# BSPD_V2_1.net
KiCad netlist of a schematic drawn in Altium Designer
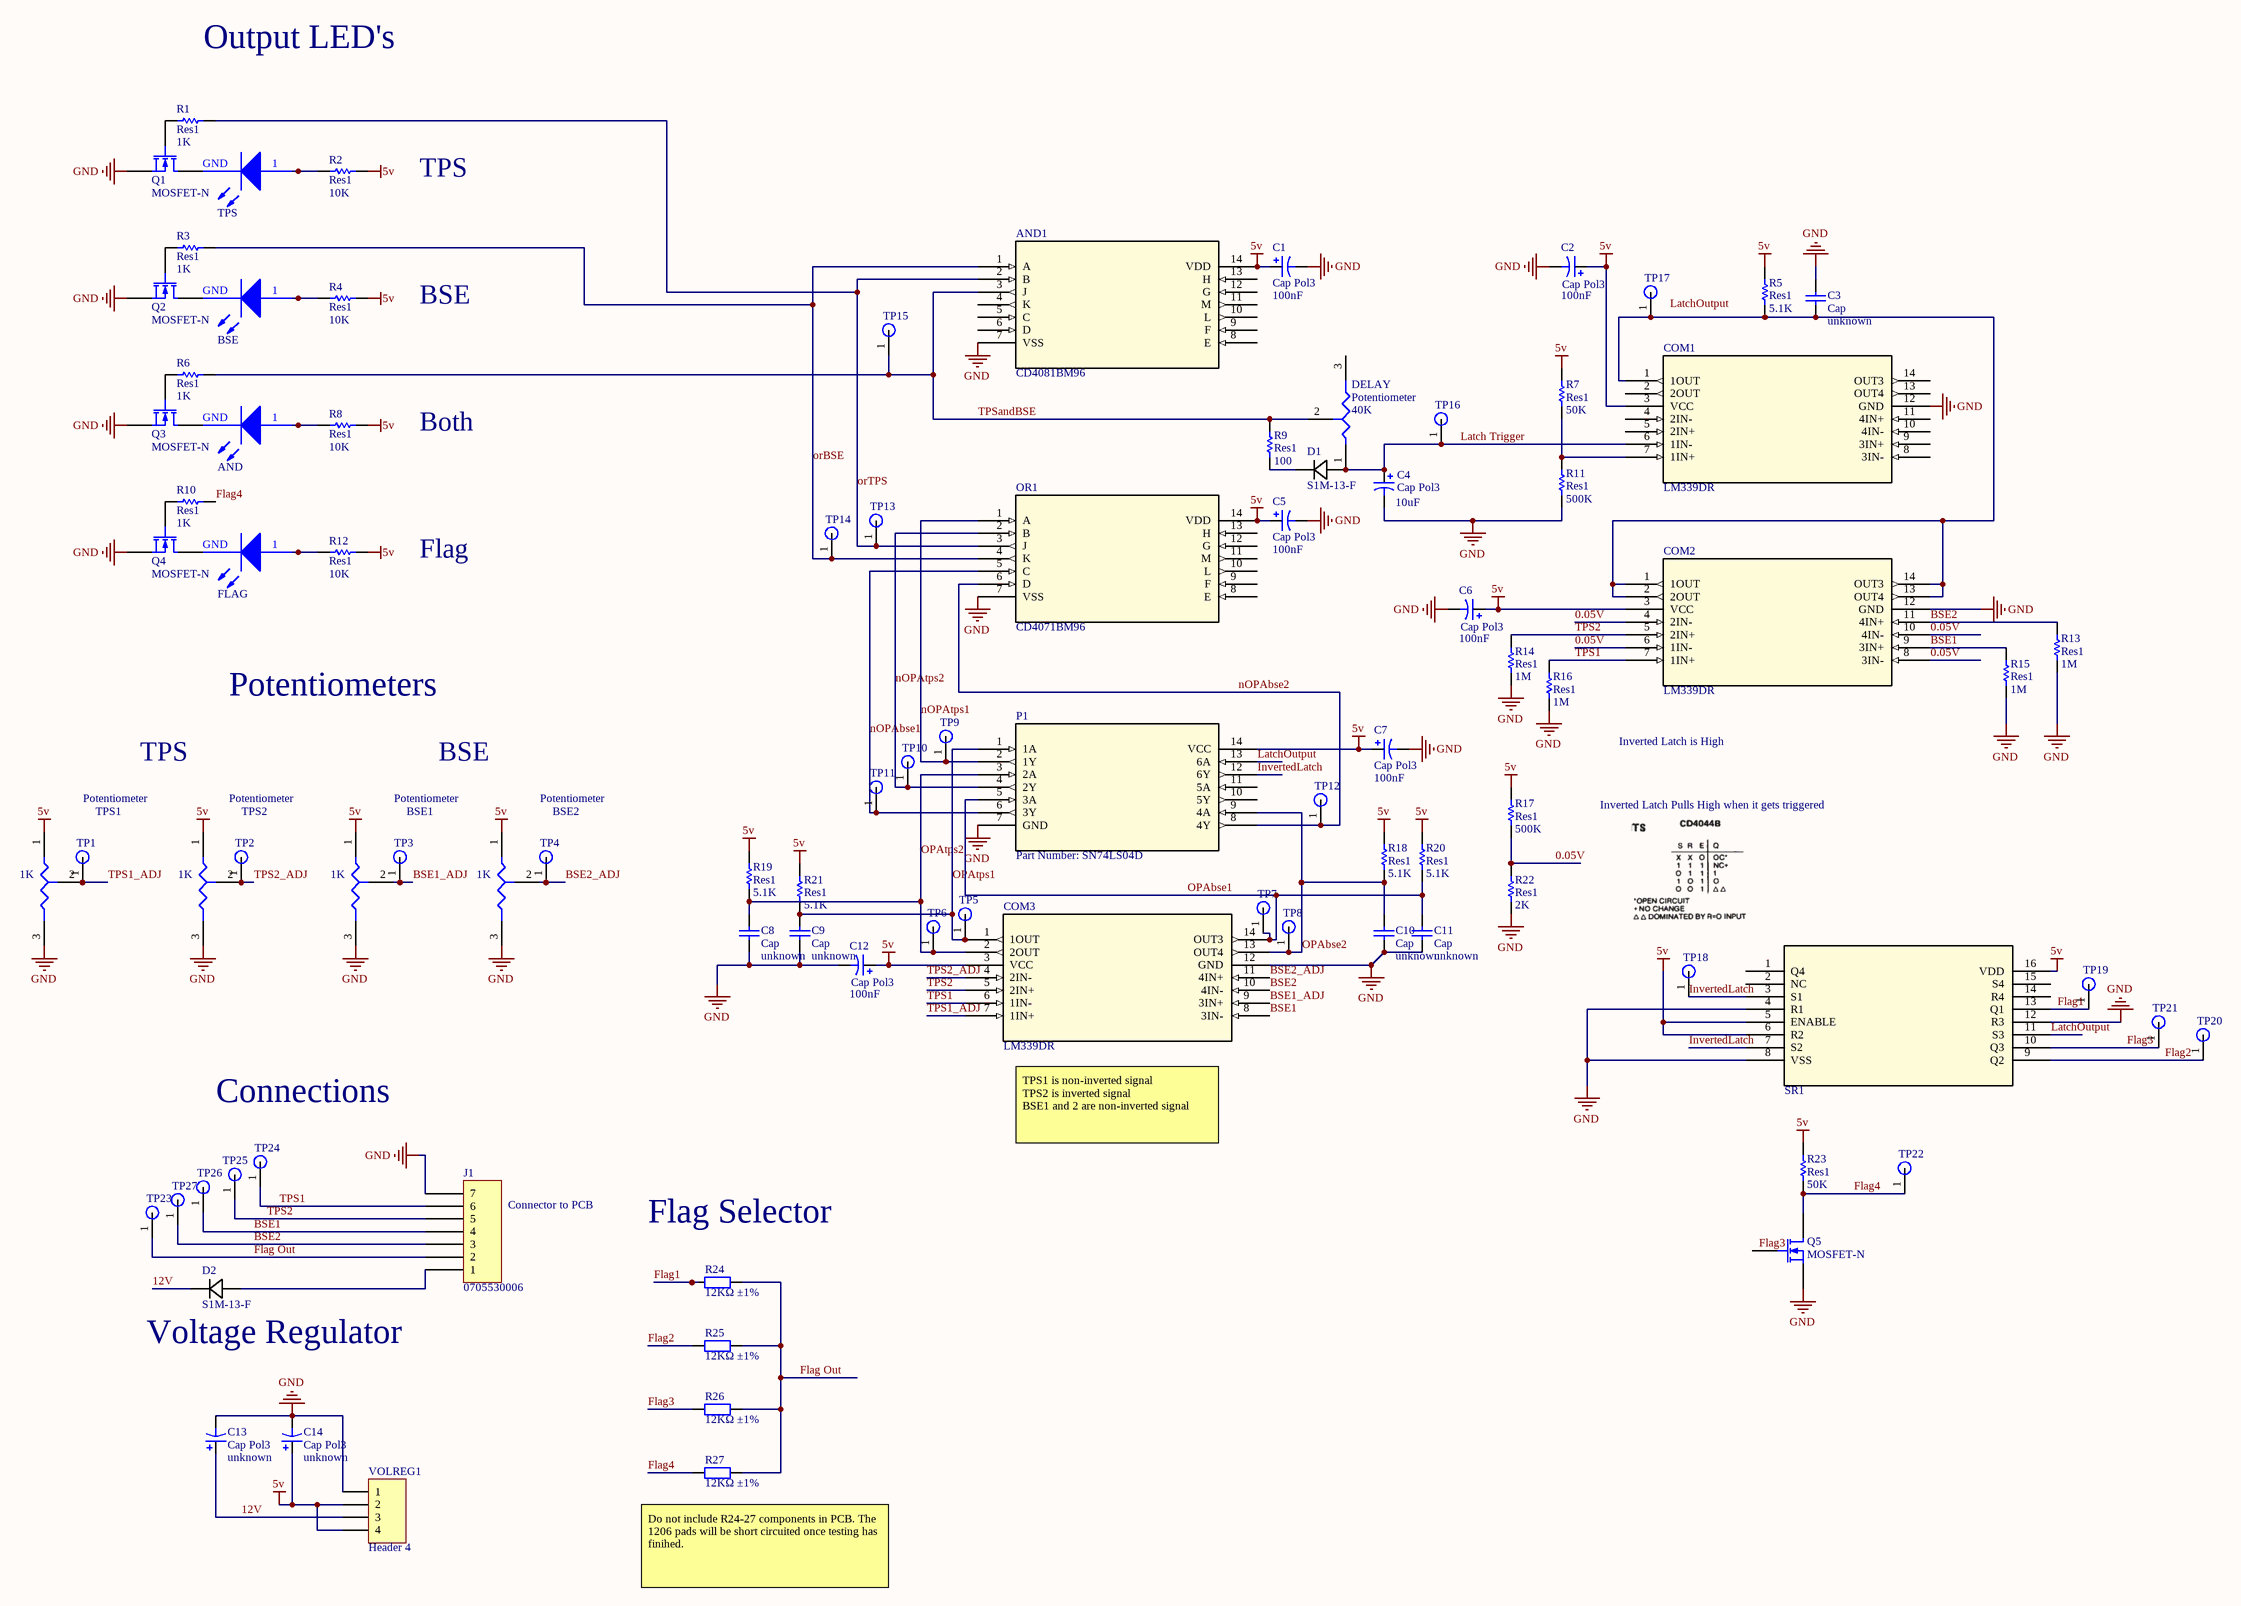
[diagram p0: BSPD_V2.1.SchDoc]

(export (version "E")
  (design (tool "Eeschema 10.0.6"))
  (components
    (comp (ref "AND")
      (value "Green Led")
      (footprint "Single_Color_LED")
      (description "DK: 1497-1160-1-ND Ζ MF: XZM2DG45SB")
      (libsource (lib "AltiumDesigner") (part "Green_LED"))
    )
    (comp (ref "AND1")
      (value "CD4081BM96")
      (footprint "D14")
      (description "Imported")
      (libsource (lib "AltiumDesigner") (part "CD4081BM96"))
    )
    (comp (ref "BSE")
      (value "Green Led")
      (footprint "Single_Color_LED")
      (description "DK: 1497-1160-1-ND Ζ MF: XZM2DG45SB")
      (libsource (lib "AltiumDesigner") (part "Green_LED"))
    )
    (comp (ref "BSE1")
      (value "Potentiometer")
      (footprint "Potentiometers")
      (description "Tapped Resistor")
      (fields (field (name "ALTIUM_VALUE") "1K") (field (name "PUBLISHER") "Altium Limited"))
      (libsource (lib "BSPD_Library") (part "Potentiometer"))
    )
    (comp (ref "BSE2")
      (value "Potentiometer")
      (footprint "Potentiometers")
      (description "Tapped Resistor")
      (fields (field (name "ALTIUM_VALUE") "1K") (field (name "PUBLISHER") "Altium Limited"))
      (libsource (lib "BSPD_Library") (part "Potentiometer"))
    )
    (comp (ref "C1")
      (value "Cap Pol3")
      (footprint "RC0805N")
      (description "Polarized Capacitor (Surface Mount)")
      (fields (field (name "ALTIUM_VALUE") "100nF") (field (name "PUBLISHER") "Altium Limited"))
      (libsource (lib "Miscellaneous Devices") (part "Cap Pol3"))
    )
    (comp (ref "C2")
      (value "Cap Pol3")
      (footprint "RC0805N")
      (description "Polarized Capacitor (Surface Mount)")
      (fields (field (name "ALTIUM_VALUE") "100nF") (field (name "PUBLISHER") "Altium Limited"))
      (libsource (lib "Miscellaneous Devices") (part "Cap Pol3"))
    )
    (comp (ref "C3")
      (value "Cap")
      (footprint "RC0805N")
      (description "Capacitor")
      (fields (field (name "ALTIUM_VALUE") "unknown") (field (name "PUBLISHER") "Altium Limited"))
      (libsource (lib "Miscellaneous Devices") (part "Cap"))
    )
    (comp (ref "C4")
      (value "Cap Pol3")
      (footprint "RC0805N")
      (description "Polarized Capacitor (Surface Mount)")
      (fields (field (name "ALTIUM_VALUE") "10uF") (field (name "PUBLISHER") "Altium Limited"))
      (libsource (lib "Miscellaneous Devices") (part "Cap Pol3"))
    )
    (comp (ref "C5")
      (value "Cap Pol3")
      (footprint "RC0805N")
      (description "Polarized Capacitor (Surface Mount)")
      (fields (field (name "ALTIUM_VALUE") "100nF") (field (name "PUBLISHER") "Altium Limited"))
      (libsource (lib "Miscellaneous Devices") (part "Cap Pol3"))
    )
    (comp (ref "C6")
      (value "Cap Pol3")
      (footprint "RC0805N")
      (description "Polarized Capacitor (Surface Mount)")
      (fields (field (name "ALTIUM_VALUE") "100nF") (field (name "PUBLISHER") "Altium Limited"))
      (libsource (lib "Miscellaneous Devices") (part "Cap Pol3"))
    )
    (comp (ref "C7")
      (value "Cap Pol3")
      (footprint "RC0805N")
      (description "Polarized Capacitor (Surface Mount)")
      (fields (field (name "ALTIUM_VALUE") "100nF") (field (name "PUBLISHER") "Altium Limited"))
      (libsource (lib "Miscellaneous Devices") (part "Cap Pol3"))
    )
    (comp (ref "C8")
      (value "Cap")
      (footprint "RC0805N")
      (description "Capacitor")
      (fields (field (name "ALTIUM_VALUE") "unknown") (field (name "PUBLISHER") "Altium Limited"))
      (libsource (lib "Miscellaneous Devices") (part "Cap"))
    )
    (comp (ref "C9")
      (value "Cap")
      (footprint "RC0805N")
      (description "Capacitor")
      (fields (field (name "ALTIUM_VALUE") "unknown") (field (name "PUBLISHER") "Altium Limited"))
      (libsource (lib "Miscellaneous Devices") (part "Cap"))
    )
    (comp (ref "C10")
      (value "Cap")
      (footprint "RC0805N")
      (description "Capacitor")
      (fields (field (name "ALTIUM_VALUE") "unknown") (field (name "PUBLISHER") "Altium Limited"))
      (libsource (lib "Miscellaneous Devices") (part "Cap"))
    )
    (comp (ref "C11")
      (value "Cap")
      (footprint "RC0805N")
      (description "Capacitor")
      (fields (field (name "ALTIUM_VALUE") "unknown") (field (name "PUBLISHER") "Altium Limited"))
      (libsource (lib "Miscellaneous Devices") (part "Cap"))
    )
    (comp (ref "C12")
      (value "Cap Pol3")
      (footprint "RC0805N")
      (description "Polarized Capacitor (Surface Mount)")
      (fields (field (name "ALTIUM_VALUE") "100nF") (field (name "PUBLISHER") "Altium Limited"))
      (libsource (lib "Miscellaneous Devices") (part "Cap Pol3"))
    )
    (comp (ref "C13")
      (value "Cap Pol3")
      (footprint "RC0805N")
      (description "Polarized Capacitor (Surface Mount)")
      (fields (field (name "ALTIUM_VALUE") "unknown") (field (name "PUBLISHER") "Altium Limited"))
      (libsource (lib "Miscellaneous Devices") (part "Cap Pol3"))
    )
    (comp (ref "C14")
      (value "Cap Pol3")
      (footprint "RC0805N")
      (description "Polarized Capacitor (Surface Mount)")
      (fields (field (name "ALTIUM_VALUE") "unknown") (field (name "PUBLISHER") "Altium Limited"))
      (libsource (lib "Miscellaneous Devices") (part "Cap Pol3"))
    )
    (comp (ref "COM1")
      (value "LM339DR")
      (footprint "D14")
      (description "Imported")
      (fields (field (name "MANUFACTURER") "Texas Instruments"))
      (libsource (lib "AltiumDesigner") (part "LM339DR"))
    )
    (comp (ref "COM2")
      (value "LM339DR")
      (footprint "D14")
      (description "Imported")
      (fields (field (name "MANUFACTURER") "Texas Instruments"))
      (libsource (lib "AltiumDesigner") (part "LM339DR"))
    )
    (comp (ref "COM3")
      (value "LM339DR")
      (footprint "D14")
      (description "Imported")
      (fields (field (name "MANUFACTURER") "Texas Instruments"))
      (libsource (lib "AltiumDesigner") (part "LM339DR"))
    )
    (comp (ref "D1")
      (value "S1M-13-F")
      (footprint "DIODE")
      (description "Imported")
      (libsource (lib "AltiumDesigner") (part "S1M-13-F"))
    )
    (comp (ref "D2")
      (value "S1M-13-F")
      (footprint "DIODE")
      (description "Imported")
      (libsource (lib "AltiumDesigner") (part "S1M-13-F"))
    )
    (comp (ref "DELAY")
      (value "Potentiometer")
      (footprint "Potentiometers")
      (description "Tapped Resistor")
      (fields (field (name "ALTIUM_VALUE") "40K") (field (name "PUBLISHER") "Altium Limited"))
      (libsource (lib "BSPD_Library") (part "Potentiometer"))
    )
    (comp (ref "FLAG")
      (value "Green Led")
      (footprint "Single_Color_LED")
      (description "DK: 1497-1160-1-ND Ζ MF: XZM2DG45SB")
      (libsource (lib "AltiumDesigner") (part "Green_LED"))
    )
    (comp (ref "J1")
      (value "0705530006")
      (footprint "MOLEX SDA-70553-7PIN")
      (description "CONN HEADER R/A 7POS 2.54MM")
      (fields (field (name "MANUFACTURER") "Molex"))
      (libsource (lib "Celestial Altium Library - altium_library") (part "7 Pin"))
    )
    (comp (ref "OR1")
      (value "CD4071BM96")
      (footprint "D14")
      (description "Imported")
      (libsource (lib "AltiumDesigner") (part "CD4071BM96"))
    )
    (comp (ref "P1")
      (value "Part Number: SN74LS04D")
      (footprint "D14")
      (description "No Description Available")
      (fields
        (field (name "MANUFACTURER_PART_NUMBER") "SN74LS04D")
        (field (name "COPYRIGHT") "Copyright (C) 2018 Accelerated Designs. All rights reserved")
      )
      (libsource (lib "AltiumDesigner") (part "SN74LS04D"))
    )
    (comp (ref "Q1")
      (value "MOSFET-N")
      (footprint "SOT-23-3")
      (description "N-Channel MOSFET")
      (fields (field (name "PUBLISHER") "Altium Limited"))
      (libsource (lib "Miscellaneous Devices") (part "MOSFET-N"))
    )
    (comp (ref "Q2")
      (value "MOSFET-N")
      (footprint "SOT-23-3")
      (description "N-Channel MOSFET")
      (fields (field (name "PUBLISHER") "Altium Limited"))
      (libsource (lib "Miscellaneous Devices") (part "MOSFET-N"))
    )
    (comp (ref "Q3")
      (value "MOSFET-N")
      (footprint "SOT-23-3")
      (description "N-Channel MOSFET")
      (fields (field (name "PUBLISHER") "Altium Limited"))
      (libsource (lib "Miscellaneous Devices") (part "MOSFET-N"))
    )
    (comp (ref "Q4")
      (value "MOSFET-N")
      (footprint "SOT-23-3")
      (description "N-Channel MOSFET")
      (fields (field (name "PUBLISHER") "Altium Limited"))
      (libsource (lib "Miscellaneous Devices") (part "MOSFET-N"))
    )
    (comp (ref "Q5")
      (value "MOSFET-N")
      (footprint "SOT-23-3")
      (description "N-Channel MOSFET")
      (fields (field (name "PUBLISHER") "Altium Limited"))
      (libsource (lib "Miscellaneous Devices") (part "MOSFET-N"))
    )
    (comp (ref "R1")
      (value "Res1")
      (footprint "RC0805N")
      (description "Resistor")
      (fields (field (name "ALTIUM_VALUE") "1K") (field (name "PUBLISHER") "Altium Limited"))
      (libsource (lib "Miscellaneous Devices") (part "Res1"))
    )
    (comp (ref "R2")
      (value "Res1")
      (footprint "RC0805N")
      (description "Resistor")
      (fields (field (name "ALTIUM_VALUE") "10K") (field (name "PUBLISHER") "Altium Limited"))
      (libsource (lib "Miscellaneous Devices") (part "Res1"))
    )
    (comp (ref "R3")
      (value "Res1")
      (footprint "RC0805N")
      (description "Resistor")
      (fields (field (name "ALTIUM_VALUE") "1K") (field (name "PUBLISHER") "Altium Limited"))
      (libsource (lib "Miscellaneous Devices") (part "Res1"))
    )
    (comp (ref "R4")
      (value "Res1")
      (footprint "RC0805N")
      (description "Resistor")
      (fields (field (name "ALTIUM_VALUE") "10K") (field (name "PUBLISHER") "Altium Limited"))
      (libsource (lib "Miscellaneous Devices") (part "Res1"))
    )
    (comp (ref "R5")
      (value "Res1")
      (footprint "RC0805N")
      (description "Resistor")
      (fields (field (name "ALTIUM_VALUE") "5.1K") (field (name "PUBLISHER") "Altium Limited"))
      (libsource (lib "Miscellaneous Devices") (part "Res1"))
    )
    (comp (ref "R6")
      (value "Res1")
      (footprint "RC0805N")
      (description "Resistor")
      (fields (field (name "ALTIUM_VALUE") "1K") (field (name "PUBLISHER") "Altium Limited"))
      (libsource (lib "Miscellaneous Devices") (part "Res1"))
    )
    (comp (ref "R7")
      (value "Res1")
      (footprint "RC0805N")
      (description "Resistor")
      (fields (field (name "ALTIUM_VALUE") "50K") (field (name "PUBLISHER") "Altium Limited"))
      (libsource (lib "Miscellaneous Devices") (part "Res1"))
    )
    (comp (ref "R8")
      (value "Res1")
      (footprint "RC0805N")
      (description "Resistor")
      (fields (field (name "ALTIUM_VALUE") "10K") (field (name "PUBLISHER") "Altium Limited"))
      (libsource (lib "Miscellaneous Devices") (part "Res1"))
    )
    (comp (ref "R9")
      (value "Res1")
      (footprint "RC0805N")
      (description "Resistor")
      (fields (field (name "ALTIUM_VALUE") "100") (field (name "PUBLISHER") "Altium Limited"))
      (libsource (lib "Miscellaneous Devices") (part "Res1"))
    )
    (comp (ref "R10")
      (value "Res1")
      (footprint "RC0805N")
      (description "Resistor")
      (fields (field (name "ALTIUM_VALUE") "1K") (field (name "PUBLISHER") "Altium Limited"))
      (libsource (lib "Miscellaneous Devices") (part "Res1"))
    )
    (comp (ref "R11")
      (value "Res1")
      (footprint "RC0805N")
      (description "Resistor")
      (fields (field (name "ALTIUM_VALUE") "500K") (field (name "PUBLISHER") "Altium Limited"))
      (libsource (lib "Miscellaneous Devices") (part "Res1"))
    )
    (comp (ref "R12")
      (value "Res1")
      (footprint "RC0805N")
      (description "Resistor")
      (fields (field (name "ALTIUM_VALUE") "10K") (field (name "PUBLISHER") "Altium Limited"))
      (libsource (lib "Miscellaneous Devices") (part "Res1"))
    )
    (comp (ref "R13")
      (value "Res1")
      (footprint "RC0805N")
      (description "Resistor")
      (fields (field (name "ALTIUM_VALUE") "1M") (field (name "PUBLISHER") "Altium Limited"))
      (libsource (lib "Miscellaneous Devices") (part "Res1"))
    )
    (comp (ref "R14")
      (value "Res1")
      (footprint "RC0805N")
      (description "Resistor")
      (fields (field (name "ALTIUM_VALUE") "1M") (field (name "PUBLISHER") "Altium Limited"))
      (libsource (lib "Miscellaneous Devices") (part "Res1"))
    )
    (comp (ref "R15")
      (value "Res1")
      (footprint "RC0805N")
      (description "Resistor")
      (fields (field (name "ALTIUM_VALUE") "1M") (field (name "PUBLISHER") "Altium Limited"))
      (libsource (lib "Miscellaneous Devices") (part "Res1"))
    )
    (comp (ref "R16")
      (value "Res1")
      (footprint "RC0805N")
      (description "Resistor")
      (fields (field (name "ALTIUM_VALUE") "1M") (field (name "PUBLISHER") "Altium Limited"))
      (libsource (lib "Miscellaneous Devices") (part "Res1"))
    )
    (comp (ref "R17")
      (value "Res1")
      (footprint "RC0805N")
      (description "Resistor")
      (fields (field (name "ALTIUM_VALUE") "500K") (field (name "PUBLISHER") "Altium Limited"))
      (libsource (lib "Miscellaneous Devices") (part "Res1"))
    )
    (comp (ref "R18")
      (value "Res1")
      (footprint "RC0805N")
      (description "Resistor")
      (fields (field (name "ALTIUM_VALUE") "5.1K") (field (name "PUBLISHER") "Altium Limited"))
      (libsource (lib "Miscellaneous Devices") (part "Res1"))
    )
    (comp (ref "R19")
      (value "Res1")
      (footprint "RC0805N")
      (description "Resistor")
      (fields (field (name "ALTIUM_VALUE") "5.1K") (field (name "PUBLISHER") "Altium Limited"))
      (libsource (lib "Miscellaneous Devices") (part "Res1"))
    )
    (comp (ref "R20")
      (value "Res1")
      (footprint "RC0805N")
      (description "Resistor")
      (fields (field (name "ALTIUM_VALUE") "5.1K") (field (name "PUBLISHER") "Altium Limited"))
      (libsource (lib "Miscellaneous Devices") (part "Res1"))
    )
    (comp (ref "R21")
      (value "Res1")
      (footprint "RC0805N")
      (description "Resistor")
      (fields (field (name "ALTIUM_VALUE") "5.1K") (field (name "PUBLISHER") "Altium Limited"))
      (libsource (lib "Miscellaneous Devices") (part "Res1"))
    )
    (comp (ref "R22")
      (value "Res1")
      (footprint "RC0805N")
      (description "Resistor")
      (fields (field (name "ALTIUM_VALUE") "2K") (field (name "PUBLISHER") "Altium Limited"))
      (libsource (lib "Miscellaneous Devices") (part "Res1"))
    )
    (comp (ref "R23")
      (value "Res1")
      (footprint "RC0805N")
      (description "Resistor")
      (fields (field (name "ALTIUM_VALUE") "50K") (field (name "PUBLISHER") "Altium Limited"))
      (libsource (lib "Miscellaneous Devices") (part "Res1"))
    )
    (comp (ref "R24")
      (value "12KΩ ±1%")
      (footprint "0805_R")
      (description "Chip resistor")
      (fields (field (name "MANUFACTURER") "Uniroyal Elec") (field (name "POWER") "1/8W"))
      (libsource (lib "RES") (part "0805 12K (1202) 1%"))
    )
    (comp (ref "R25")
      (value "12KΩ ±1%")
      (footprint "0805_R")
      (description "Chip resistor")
      (fields (field (name "MANUFACTURER") "Uniroyal Elec") (field (name "POWER") "1/8W"))
      (libsource (lib "RES") (part "0805 12K (1202) 1%"))
    )
    (comp (ref "R26")
      (value "12KΩ ±1%")
      (footprint "0805_R")
      (description "Chip resistor")
      (fields (field (name "MANUFACTURER") "Uniroyal Elec") (field (name "POWER") "1/8W"))
      (libsource (lib "RES") (part "0805 12K (1202) 1%"))
    )
    (comp (ref "R27")
      (value "12KΩ ±1%")
      (footprint "0805_R")
      (description "Chip resistor")
      (fields (field (name "MANUFACTURER") "Uniroyal Elec") (field (name "POWER") "1/8W"))
      (libsource (lib "RES") (part "0805 12K (1202) 1%"))
    )
    (comp (ref "SR1")
      (value "CD4044BNSR")
      (footprint "NS16")
      (description "IC QUAD NAND R/S LATCH 16SO")
      (libsource (lib "QFSAE_ELEC") (part "SR Latch Quad"))
    )
    (comp (ref "TP1") (value "Test Point") (footprint "TP1") (libsource (lib "ethan") (part "TP1")))
    (comp (ref "TP2") (value "Test Point") (footprint "TP1") (libsource (lib "ethan") (part "TP1")))
    (comp (ref "TP3") (value "Test Point") (footprint "TP1") (libsource (lib "ethan") (part "TP1")))
    (comp (ref "TP4") (value "Test Point") (footprint "TP1") (libsource (lib "ethan") (part "TP1")))
    (comp (ref "TP5") (value "Test Point") (footprint "TP1") (libsource (lib "ethan") (part "TP1")))
    (comp (ref "TP6") (value "Test Point") (footprint "TP1") (libsource (lib "ethan") (part "TP1")))
    (comp (ref "TP7") (value "Test Point") (footprint "TP1") (libsource (lib "ethan") (part "TP1")))
    (comp (ref "TP8") (value "Test Point") (footprint "TP1") (libsource (lib "ethan") (part "TP1")))
    (comp (ref "TP9") (value "Test Point") (footprint "TP1") (libsource (lib "ethan") (part "TP1")))
    (comp (ref "TP10") (value "Test Point") (footprint "TP1") (libsource (lib "ethan") (part "TP1")))
    (comp (ref "TP11") (value "Test Point") (footprint "TP1") (libsource (lib "ethan") (part "TP1")))
    (comp (ref "TP12") (value "Test Point") (footprint "TP1") (libsource (lib "ethan") (part "TP1")))
    (comp (ref "TP13") (value "Test Point") (footprint "TP1") (libsource (lib "ethan") (part "TP1")))
    (comp (ref "TP14") (value "Test Point") (footprint "TP1") (libsource (lib "ethan") (part "TP1")))
    (comp (ref "TP15") (value "Test Point") (footprint "TP1") (libsource (lib "ethan") (part "TP1")))
    (comp (ref "TP16") (value "Test Point") (footprint "TP1") (libsource (lib "ethan") (part "TP1")))
    (comp (ref "TP17") (value "Test Point") (footprint "TP1") (libsource (lib "ethan") (part "TP1")))
    (comp (ref "TP18") (value "Test Point") (footprint "TP1") (libsource (lib "ethan") (part "TP1")))
    (comp (ref "TP19") (value "Test Point") (footprint "TP1") (libsource (lib "ethan") (part "TP1")))
    (comp (ref "TP20") (value "Test Point") (footprint "TP1") (libsource (lib "ethan") (part "TP1")))
    (comp (ref "TP21") (value "Test Point") (footprint "TP1") (libsource (lib "ethan") (part "TP1")))
    (comp (ref "TP22") (value "Test Point") (footprint "TP1") (libsource (lib "ethan") (part "TP1")))
    (comp (ref "TP23") (value "Test Point") (footprint "TP1") (libsource (lib "ethan") (part "TP1")))
    (comp (ref "TP24") (value "Test Point") (footprint "TP1") (libsource (lib "ethan") (part "TP1")))
    (comp (ref "TP25") (value "Test Point") (footprint "TP1") (libsource (lib "ethan") (part "TP1")))
    (comp (ref "TP26") (value "Test Point") (footprint "TP1") (libsource (lib "ethan") (part "TP1")))
    (comp (ref "TP27") (value "Test Point") (footprint "TP1") (libsource (lib "ethan") (part "TP1")))
    (comp (ref "TPS")
      (value "Green Led")
      (footprint "Single_Color_LED")
      (description "DK: 1497-1160-1-ND Ζ MF: XZM2DG45SB")
      (libsource (lib "AltiumDesigner") (part "Green_LED"))
    )
    (comp (ref "TPS1")
      (value "Potentiometer")
      (footprint "Potentiometers")
      (description "Tapped Resistor")
      (fields (field (name "ALTIUM_VALUE") "1K") (field (name "PUBLISHER") "Altium Limited"))
      (libsource (lib "BSPD_Library") (part "Potentiometer"))
    )
    (comp (ref "TPS2")
      (value "Potentiometer")
      (footprint "Potentiometers")
      (description "Tapped Resistor")
      (fields (field (name "ALTIUM_VALUE") "1K") (field (name "PUBLISHER") "Altium Limited"))
      (libsource (lib "BSPD_Library") (part "Potentiometer"))
    )
    (comp (ref "VOLREG1")
      (value "Header 4")
      (footprint "LM1117IMPX-5.0/NOPB")
      (description "Header, 4-Pin")
      (fields (field (name "PUBLISHER") "Altium Limited"))
      (libsource (lib "Miscellaneous Connectors") (part "Header 4"))
    )
  )
  (nets
    (net (code "1") (name "/0.05V") (class "Default")
      (node (ref "COM2") (pin "10") (pinfunction "4IN-_10") (pintype "input"))
      (node (ref "COM2") (pin "4") (pinfunction "2IN-_4") (pintype "input"))
      (node (ref "COM2") (pin "6") (pinfunction "1IN-_6") (pintype "input"))
      (node (ref "COM2") (pin "8") (pinfunction "3IN-_8") (pintype "input"))
      (node (ref "R17") (pin "2") (pinfunction "2_2") (pintype "passive"))
      (node (ref "R22") (pin "1") (pinfunction "1_1") (pintype "passive"))
    )
    (net (code "2") (name "/12V") (class "Default")
      (node (ref "C13") (pin "1") (pinfunction "1_1") (pintype "passive"))
      (node (ref "D2") (pin "1") (pinfunction "1_1") (pintype "passive"))
      (node (ref "VOLREG1") (pin "3") (pinfunction "3_3") (pintype "passive"))
    )
    (net (code "3") (name "/BSE1") (class "Default")
      (node (ref "COM2") (pin "9") (pinfunction "3IN+_9") (pintype "input"))
      (node (ref "COM3") (pin "8") (pinfunction "3IN-_8") (pintype "input"))
      (node (ref "J1") (pin "4") (pinfunction "4_4") (pintype "passive"))
      (node (ref "R15") (pin "1") (pinfunction "1_1") (pintype "passive"))
      (node (ref "TP26") (pin "1") (pinfunction "1_1") (pintype "passive"))
    )
    (net (code "4") (name "/BSE1_ADJ") (class "Default")
      (node (ref "BSE1") (pin "2") (pinfunction "TAP_2") (pintype "passive"))
      (node (ref "COM3") (pin "9") (pinfunction "3IN+_9") (pintype "input"))
      (node (ref "TP3") (pin "1") (pinfunction "1_1") (pintype "passive"))
    )
    (net (code "5") (name "/BSE2") (class "Default")
      (node (ref "COM2") (pin "11") (pinfunction "4IN+_11") (pintype "input"))
      (node (ref "COM3") (pin "10") (pinfunction "4IN-_10") (pintype "input"))
      (node (ref "J1") (pin "3") (pinfunction "3_3") (pintype "passive"))
      (node (ref "R13") (pin "1") (pinfunction "1_1") (pintype "passive"))
      (node (ref "TP27") (pin "1") (pinfunction "1_1") (pintype "passive"))
    )
    (net (code "6") (name "/BSE2_ADJ") (class "Default")
      (node (ref "BSE2") (pin "2") (pinfunction "TAP_2") (pintype "passive"))
      (node (ref "COM3") (pin "11") (pinfunction "4IN+_11") (pintype "input"))
      (node (ref "TP4") (pin "1") (pinfunction "1_1") (pintype "passive"))
    )
    (net (code "7") (name "/Flag Out") (class "Default")
      (node (ref "J1") (pin "2") (pinfunction "2_2") (pintype "passive"))
      (node (ref "R24") (pin "2") (pinfunction "2_2") (pintype "passive"))
      (node (ref "R25") (pin "2") (pinfunction "2_2") (pintype "passive"))
      (node (ref "R26") (pin "2") (pinfunction "2_2") (pintype "passive"))
      (node (ref "R27") (pin "2") (pinfunction "2_2") (pintype "passive"))
      (node (ref "TP23") (pin "1") (pinfunction "1_1") (pintype "passive"))
    )
    (net (code "8") (name "/Flag1") (class "Default")
      (node (ref "R24") (pin "1") (pinfunction "1_1") (pintype "passive"))
      (node (ref "SR1") (pin "13") (pinfunction "Q1_13") (pintype "passive"))
      (node (ref "TP19") (pin "1") (pinfunction "1_1") (pintype "passive"))
    )
    (net (code "9") (name "/Flag2") (class "Default")
      (node (ref "R25") (pin "1") (pinfunction "1_1") (pintype "passive"))
      (node (ref "SR1") (pin "9") (pinfunction "Q2_9") (pintype "passive"))
      (node (ref "TP20") (pin "1") (pinfunction "1_1") (pintype "passive"))
    )
    (net (code "10") (name "/Flag3") (class "Default")
      (node (ref "R26") (pin "1") (pinfunction "1_1") (pintype "passive"))
      (node (ref "SR1") (pin "10") (pinfunction "Q3_10") (pintype "passive"))
      (node (ref "TP21") (pin "1") (pinfunction "1_1") (pintype "passive"))
    )
    (net (code "11") (name "/Flag4") (class "Default")
      (node (ref "Q5") (pin "1") (pinfunction "D_1") (pintype "passive"))
      (node (ref "R10") (pin "1") (pinfunction "1_1") (pintype "passive"))
      (node (ref "R23") (pin "1") (pinfunction "1_1") (pintype "passive"))
      (node (ref "R27") (pin "1") (pinfunction "1_1") (pintype "passive"))
      (node (ref "TP22") (pin "1") (pinfunction "1_1") (pintype "passive"))
    )
    (net (code "12") (name "/InvertedLatch") (class "Default")
      (node (ref "P1") (pin "12") (pinfunction "6Y_12") (pintype "output"))
      (node (ref "SR1") (pin "3") (pinfunction "S1_3") (pintype "passive"))
      (node (ref "SR1") (pin "7") (pinfunction "S2_7") (pintype "passive"))
      (node (ref "TP18") (pin "1") (pinfunction "1_1") (pintype "passive"))
    )
    (net (code "13") (name "/Latch Trigger") (class "Default")
      (node (ref "C4") (pin "1") (pinfunction "1_1") (pintype "passive"))
      (node (ref "COM1") (pin "6") (pinfunction "1IN-_6") (pintype "input"))
      (node (ref "D1") (pin "2") (pinfunction "2_2") (pintype "passive"))
      (node (ref "DELAY") (pin "1") (pinfunction "A_1") (pintype "passive"))
      (node (ref "TP16") (pin "1") (pinfunction "1_1") (pintype "passive"))
    )
    (net (code "14") (name "/LatchOutput") (class "Default")
      (node (ref "P1") (pin "13") (pinfunction "6A_13") (pintype "input"))
      (node (ref "SR1") (pin "11") (pinfunction "S3_11") (pintype "passive"))
    )
    (net (code "15") (name "/OPAbse1") (class "Default")
      (node (ref "C11") (pin "2") (pinfunction "2_2") (pintype "passive"))
      (node (ref "COM3") (pin "14") (pinfunction "OUT3_14") (pintype "output"))
      (node (ref "P1") (pin "5") (pinfunction "3A_5") (pintype "input"))
      (node (ref "R20") (pin "2") (pinfunction "2_2") (pintype "passive"))
      (node (ref "TP7") (pin "1") (pinfunction "1_1") (pintype "passive"))
    )
    (net (code "16") (name "/OPAbse2") (class "Default")
      (node (ref "C10") (pin "2") (pinfunction "2_2") (pintype "passive"))
      (node (ref "COM3") (pin "13") (pinfunction "OUT4_13") (pintype "output"))
      (node (ref "P1") (pin "9") (pinfunction "4A_9") (pintype "input"))
      (node (ref "R18") (pin "2") (pinfunction "2_2") (pintype "passive"))
      (node (ref "TP8") (pin "1") (pinfunction "1_1") (pintype "passive"))
    )
    (net (code "17") (name "/OPAtps1") (class "Default")
      (node (ref "C9") (pin "2") (pinfunction "2_2") (pintype "passive"))
      (node (ref "COM3") (pin "1") (pinfunction "1OUT_1") (pintype "output"))
      (node (ref "P1") (pin "1") (pinfunction "1A_1") (pintype "input"))
      (node (ref "R21") (pin "2") (pinfunction "2_2") (pintype "passive"))
      (node (ref "TP5") (pin "1") (pinfunction "1_1") (pintype "passive"))
    )
    (net (code "18") (name "/OPAtps2") (class "Default")
      (node (ref "C8") (pin "2") (pinfunction "2_2") (pintype "passive"))
      (node (ref "COM3") (pin "2") (pinfunction "2OUT_2") (pintype "output"))
      (node (ref "P1") (pin "3") (pinfunction "2A_3") (pintype "input"))
      (node (ref "R19") (pin "2") (pinfunction "2_2") (pintype "passive"))
      (node (ref "TP6") (pin "1") (pinfunction "1_1") (pintype "passive"))
    )
    (net (code "19") (name "/TPS1") (class "Default")
      (node (ref "COM2") (pin "7") (pinfunction "1IN+_7") (pintype "input"))
      (node (ref "COM3") (pin "6") (pinfunction "1IN-_6") (pintype "input"))
      (node (ref "J1") (pin "6") (pinfunction "6_6") (pintype "passive"))
      (node (ref "R16") (pin "1") (pinfunction "1_1") (pintype "passive"))
      (node (ref "TP24") (pin "1") (pinfunction "1_1") (pintype "passive"))
    )
    (net (code "20") (name "/TPS1_ADJ") (class "Default")
      (node (ref "COM3") (pin "7") (pinfunction "1IN+_7") (pintype "input"))
      (node (ref "TP1") (pin "1") (pinfunction "1_1") (pintype "passive"))
      (node (ref "TPS1") (pin "2") (pinfunction "TAP_2") (pintype "passive"))
    )
    (net (code "21") (name "/TPS2") (class "Default")
      (node (ref "COM2") (pin "5") (pinfunction "2IN+_5") (pintype "input"))
      (node (ref "COM3") (pin "5") (pinfunction "2IN+_5") (pintype "input"))
      (node (ref "J1") (pin "5") (pinfunction "5_5") (pintype "passive"))
      (node (ref "R14") (pin "1") (pinfunction "1_1") (pintype "passive"))
      (node (ref "TP25") (pin "1") (pinfunction "1_1") (pintype "passive"))
    )
    (net (code "22") (name "/TPS2_ADJ") (class "Default")
      (node (ref "COM3") (pin "4") (pinfunction "2IN-_4") (pintype "input"))
      (node (ref "TP2") (pin "1") (pinfunction "1_1") (pintype "passive"))
      (node (ref "TPS2") (pin "2") (pinfunction "TAP_2") (pintype "passive"))
    )
    (net (code "23") (name "/TPSandBSE") (class "Default")
      (node (ref "AND1") (pin "3") (pinfunction "J_3") (pintype "output"))
      (node (ref "DELAY") (pin "2") (pinfunction "TAP_2") (pintype "passive"))
      (node (ref "R6") (pin "1") (pinfunction "1_1") (pintype "passive"))
      (node (ref "R9") (pin "1") (pinfunction "1_1") (pintype "passive"))
      (node (ref "TP15") (pin "1") (pinfunction "1_1") (pintype "passive"))
    )
    (net (code "24") (name "/nOPAbse1") (class "Default")
      (node (ref "OR1") (pin "5") (pinfunction "C_5") (pintype "input"))
      (node (ref "P1") (pin "6") (pinfunction "3Y_6") (pintype "output"))
      (node (ref "TP11") (pin "1") (pinfunction "1_1") (pintype "passive"))
    )
    (net (code "25") (name "/nOPAbse2") (class "Default")
      (node (ref "OR1") (pin "6") (pinfunction "D_6") (pintype "input"))
      (node (ref "P1") (pin "8") (pinfunction "4Y_8") (pintype "output"))
      (node (ref "TP12") (pin "1") (pinfunction "1_1") (pintype "passive"))
    )
    (net (code "26") (name "/nOPAtps1") (class "Default")
      (node (ref "OR1") (pin "1") (pinfunction "A_1") (pintype "input"))
      (node (ref "P1") (pin "2") (pinfunction "1Y_2") (pintype "output"))
      (node (ref "TP9") (pin "1") (pinfunction "1_1") (pintype "passive"))
    )
    (net (code "27") (name "/nOPAtps2") (class "Default")
      (node (ref "OR1") (pin "2") (pinfunction "B_2") (pintype "input"))
      (node (ref "P1") (pin "4") (pinfunction "2Y_4") (pintype "output"))
      (node (ref "TP10") (pin "1") (pinfunction "1_1") (pintype "passive"))
    )
    (net (code "28") (name "/orBSE") (class "Default")
      (node (ref "AND1") (pin "1") (pinfunction "A_1") (pintype "input"))
      (node (ref "OR1") (pin "4") (pinfunction "K_4") (pintype "output"))
      (node (ref "R3") (pin "1") (pinfunction "1_1") (pintype "passive"))
      (node (ref "TP14") (pin "1") (pinfunction "1_1") (pintype "passive"))
    )
    (net (code "29") (name "/orTPS") (class "Default")
      (node (ref "AND1") (pin "2") (pinfunction "B_2") (pintype "input"))
      (node (ref "OR1") (pin "3") (pinfunction "J_3") (pintype "output"))
      (node (ref "R1") (pin "1") (pinfunction "1_1") (pintype "passive"))
      (node (ref "TP13") (pin "1") (pinfunction "1_1") (pintype "passive"))
    )
    (net (code "30") (name "5v") (class "Default")
      (node (ref "AND1") (pin "14") (pinfunction "VDD_14") (pintype "passive"))
      (node (ref "BSE1") (pin "1") (pinfunction "A_1") (pintype "passive"))
      (node (ref "BSE2") (pin "1") (pinfunction "A_1") (pintype "passive"))
      (node (ref "C1") (pin "1") (pinfunction "1_1") (pintype "passive"))
      (node (ref "C12") (pin "1") (pinfunction "1_1") (pintype "passive"))
      (node (ref "C14") (pin "1") (pinfunction "1_1") (pintype "passive"))
      (node (ref "C2") (pin "1") (pinfunction "1_1") (pintype "passive"))
      (node (ref "C5") (pin "1") (pinfunction "1_1") (pintype "passive"))
      (node (ref "C6") (pin "1") (pinfunction "1_1") (pintype "passive"))
      (node (ref "C7") (pin "1") (pinfunction "1_1") (pintype "passive"))
      (node (ref "COM1") (pin "3") (pinfunction "VCC_3") (pintype "power_in"))
      (node (ref "COM2") (pin "3") (pinfunction "VCC_3") (pintype "power_in"))
      (node (ref "COM3") (pin "3") (pinfunction "VCC_3") (pintype "power_in"))
      (node (ref "OR1") (pin "14") (pinfunction "VDD_14") (pintype "passive"))
      (node (ref "P1") (pin "14") (pinfunction "VCC_14") (pintype "power_in"))
      (node (ref "R12") (pin "1") (pinfunction "1_1") (pintype "passive"))
      (node (ref "R17") (pin "1") (pinfunction "1_1") (pintype "passive"))
      (node (ref "R18") (pin "1") (pinfunction "1_1") (pintype "passive"))
      (node (ref "R19") (pin "1") (pinfunction "1_1") (pintype "passive"))
      (node (ref "R2") (pin "1") (pinfunction "1_1") (pintype "passive"))
      (node (ref "R20") (pin "1") (pinfunction "1_1") (pintype "passive"))
      (node (ref "R21") (pin "1") (pinfunction "1_1") (pintype "passive"))
      (node (ref "R23") (pin "2") (pinfunction "2_2") (pintype "passive"))
      (node (ref "R4") (pin "1") (pinfunction "1_1") (pintype "passive"))
      (node (ref "R5") (pin "1") (pinfunction "1_1") (pintype "passive"))
      (node (ref "R7") (pin "2") (pinfunction "2_2") (pintype "passive"))
      (node (ref "R8") (pin "1") (pinfunction "1_1") (pintype "passive"))
      (node (ref "SR1") (pin "16") (pinfunction "VDD_16") (pintype "power_in"))
      (node (ref "SR1") (pin "5") (pinfunction "ENABLE_5") (pintype "passive"))
      (node (ref "SR1") (pin "6") (pinfunction "R2_6") (pintype "passive"))
      (node (ref "TPS1") (pin "1") (pinfunction "A_1") (pintype "passive"))
      (node (ref "TPS2") (pin "1") (pinfunction "A_1") (pintype "passive"))
      (node (ref "VOLREG1") (pin "2") (pinfunction "2_2") (pintype "passive"))
      (node (ref "VOLREG1") (pin "4") (pinfunction "4_4") (pintype "passive"))
    )
    (net (code "31") (name "GND") (class "Default")
      (node (ref "AND1") (pin "7") (pinfunction "VSS_7") (pintype "passive"))
      (node (ref "BSE1") (pin "3") (pinfunction "B_3") (pintype "passive"))
      (node (ref "BSE2") (pin "3") (pinfunction "B_3") (pintype "passive"))
      (node (ref "C1") (pin "2") (pinfunction "2_2") (pintype "passive"))
      (node (ref "C10") (pin "1") (pinfunction "1_1") (pintype "passive"))
      (node (ref "C11") (pin "1") (pinfunction "1_1") (pintype "passive"))
      (node (ref "C12") (pin "2") (pinfunction "2_2") (pintype "passive"))
      (node (ref "C13") (pin "2") (pinfunction "2_2") (pintype "passive"))
      (node (ref "C14") (pin "2") (pinfunction "2_2") (pintype "passive"))
      (node (ref "C2") (pin "2") (pinfunction "2_2") (pintype "passive"))
      (node (ref "C3") (pin "2") (pinfunction "2_2") (pintype "passive"))
      (node (ref "C4") (pin "2") (pinfunction "2_2") (pintype "passive"))
      (node (ref "C5") (pin "2") (pinfunction "2_2") (pintype "passive"))
      (node (ref "C6") (pin "2") (pinfunction "2_2") (pintype "passive"))
      (node (ref "C7") (pin "2") (pinfunction "2_2") (pintype "passive"))
      (node (ref "C8") (pin "1") (pinfunction "1_1") (pintype "passive"))
      (node (ref "C9") (pin "1") (pinfunction "1_1") (pintype "passive"))
      (node (ref "COM1") (pin "12") (pinfunction "GND_12") (pintype "power_in"))
      (node (ref "COM2") (pin "12") (pinfunction "GND_12") (pintype "power_in"))
      (node (ref "COM3") (pin "12") (pinfunction "GND_12") (pintype "power_in"))
      (node (ref "J1") (pin "7") (pinfunction "7_7") (pintype "passive"))
      (node (ref "OR1") (pin "7") (pinfunction "VSS_7") (pintype "passive"))
      (node (ref "P1") (pin "7") (pinfunction "GND_7") (pintype "power_in"))
      (node (ref "Q1") (pin "3") (pinfunction "S_3") (pintype "passive"))
      (node (ref "Q2") (pin "3") (pinfunction "S_3") (pintype "passive"))
      (node (ref "Q3") (pin "3") (pinfunction "S_3") (pintype "passive"))
      (node (ref "Q4") (pin "3") (pinfunction "S_3") (pintype "passive"))
      (node (ref "Q5") (pin "3") (pinfunction "S_3") (pintype "passive"))
      (node (ref "R11") (pin "2") (pinfunction "2_2") (pintype "passive"))
      (node (ref "R13") (pin "2") (pinfunction "2_2") (pintype "passive"))
      (node (ref "R14") (pin "2") (pinfunction "2_2") (pintype "passive"))
      (node (ref "R15") (pin "2") (pinfunction "2_2") (pintype "passive"))
      (node (ref "R16") (pin "2") (pinfunction "2_2") (pintype "passive"))
      (node (ref "R22") (pin "2") (pinfunction "2_2") (pintype "passive"))
      (node (ref "SR1") (pin "12") (pinfunction "R3_12") (pintype "passive"))
      (node (ref "SR1") (pin "4") (pinfunction "R1_4") (pintype "passive"))
      (node (ref "SR1") (pin "8") (pinfunction "VSS_8") (pintype "power_in"))
      (node (ref "TPS1") (pin "3") (pinfunction "B_3") (pintype "passive"))
      (node (ref "TPS2") (pin "3") (pinfunction "B_3") (pintype "passive"))
      (node (ref "VOLREG1") (pin "1") (pinfunction "1_1") (pintype "passive"))
    )
    (net (code "32") (name "Net-(AND-G)") (class "Default")
      (node (ref "AND") (pin "1") (pinfunction "G_1") (pintype "power_in"))
      (node (ref "R8") (pin "2") (pinfunction "2_2") (pintype "passive"))
    )
    (net (code "33") (name "Net-(BSE-G)") (class "Default")
      (node (ref "BSE") (pin "1") (pinfunction "G_1") (pintype "power_in"))
      (node (ref "R4") (pin "2") (pinfunction "2_2") (pintype "passive"))
    )
    (net (code "34") (name "Net-(COM1-1IN+)") (class "Default")
      (node (ref "COM1") (pin "7") (pinfunction "1IN+_7") (pintype "input"))
      (node (ref "R11") (pin "1") (pinfunction "1_1") (pintype "passive"))
      (node (ref "R7") (pin "1") (pinfunction "1_1") (pintype "passive"))
    )
    (net (code "35") (name "Net-(COM1-1OUT)") (class "Default")
      (node (ref "C3") (pin "1") (pinfunction "1_1") (pintype "passive"))
      (node (ref "COM1") (pin "1") (pinfunction "1OUT_1") (pintype "output"))
      (node (ref "COM2") (pin "1") (pinfunction "1OUT_1") (pintype "output"))
      (node (ref "COM2") (pin "13") (pinfunction "OUT4_13") (pintype "output"))
      (node (ref "COM2") (pin "14") (pinfunction "OUT3_14") (pintype "output"))
      (node (ref "COM2") (pin "2") (pinfunction "2OUT_2") (pintype "output"))
      (node (ref "R5") (pin "2") (pinfunction "2_2") (pintype "passive"))
      (node (ref "TP17") (pin "1") (pinfunction "1_1") (pintype "passive"))
    )
    (net (code "36") (name "Net-(D1-Pad1)") (class "Default")
      (node (ref "D1") (pin "1") (pinfunction "1_1") (pintype "passive"))
      (node (ref "R9") (pin "2") (pinfunction "2_2") (pintype "passive"))
    )
    (net (code "37") (name "Net-(D2-Pad2)") (class "Default")
      (node (ref "D2") (pin "2") (pinfunction "2_2") (pintype "passive"))
      (node (ref "J1") (pin "1") (pinfunction "1_1") (pintype "passive"))
    )
    (net (code "38") (name "Net-(FLAG-G)") (class "Default")
      (node (ref "FLAG") (pin "1") (pinfunction "G_1") (pintype "power_in"))
      (node (ref "R12") (pin "2") (pinfunction "2_2") (pintype "passive"))
    )
    (net (code "39") (name "Net-(Q1-D)") (class "Default")
      (node (ref "Q1") (pin "1") (pinfunction "D_1") (pintype "passive"))
      (node (ref "TPS") (pin "GND") (pinfunction "GND_GND") (pintype "power_in"))
    )
    (net (code "40") (name "Net-(Q1-G)") (class "Default")
      (node (ref "Q1") (pin "2") (pinfunction "G_2") (pintype "passive"))
      (node (ref "R1") (pin "2") (pinfunction "2_2") (pintype "passive"))
    )
    (net (code "41") (name "Net-(Q2-D)") (class "Default")
      (node (ref "BSE") (pin "GND") (pinfunction "GND_GND") (pintype "power_in"))
      (node (ref "Q2") (pin "1") (pinfunction "D_1") (pintype "passive"))
    )
    (net (code "42") (name "Net-(Q2-G)") (class "Default")
      (node (ref "Q2") (pin "2") (pinfunction "G_2") (pintype "passive"))
      (node (ref "R3") (pin "2") (pinfunction "2_2") (pintype "passive"))
    )
    (net (code "43") (name "Net-(Q3-D)") (class "Default")
      (node (ref "AND") (pin "GND") (pinfunction "GND_GND") (pintype "power_in"))
      (node (ref "Q3") (pin "1") (pinfunction "D_1") (pintype "passive"))
    )
    (net (code "44") (name "Net-(Q3-G)") (class "Default")
      (node (ref "Q3") (pin "2") (pinfunction "G_2") (pintype "passive"))
      (node (ref "R6") (pin "2") (pinfunction "2_2") (pintype "passive"))
    )
    (net (code "45") (name "Net-(Q4-D)") (class "Default")
      (node (ref "FLAG") (pin "GND") (pinfunction "GND_GND") (pintype "power_in"))
      (node (ref "Q4") (pin "1") (pinfunction "D_1") (pintype "passive"))
    )
    (net (code "46") (name "Net-(Q4-G)") (class "Default")
      (node (ref "Q4") (pin "2") (pinfunction "G_2") (pintype "passive"))
      (node (ref "R10") (pin "2") (pinfunction "2_2") (pintype "passive"))
    )
    (net (code "47") (name "Net-(TPS-G)") (class "Default")
      (node (ref "R2") (pin "2") (pinfunction "2_2") (pintype "passive"))
      (node (ref "TPS") (pin "1") (pinfunction "G_1") (pintype "power_in"))
    )
    (net (code "48") (name "unconnected-(AND1-C-Pad5)") (class "Default")
      (node (ref "AND1") (pin "5") (pinfunction "C_5") (pintype "input"))
    )
    (net (code "49") (name "unconnected-(AND1-D-Pad6)") (class "Default")
      (node (ref "AND1") (pin "6") (pinfunction "D_6") (pintype "input"))
    )
    (net (code "50") (name "unconnected-(AND1-E-Pad8)") (class "Default")
      (node (ref "AND1") (pin "8") (pinfunction "E_8") (pintype "input"))
    )
    (net (code "51") (name "unconnected-(AND1-F-Pad9)") (class "Default")
      (node (ref "AND1") (pin "9") (pinfunction "F_9") (pintype "input"))
    )
    (net (code "52") (name "unconnected-(AND1-G-Pad12)") (class "Default")
      (node (ref "AND1") (pin "12") (pinfunction "G_12") (pintype "input"))
    )
    (net (code "53") (name "unconnected-(AND1-H-Pad13)") (class "Default")
      (node (ref "AND1") (pin "13") (pinfunction "H_13") (pintype "input"))
    )
    (net (code "54") (name "unconnected-(AND1-K-Pad4)") (class "Default")
      (node (ref "AND1") (pin "4") (pinfunction "K_4") (pintype "output"))
    )
    (net (code "55") (name "unconnected-(AND1-L-Pad10)") (class "Default")
      (node (ref "AND1") (pin "10") (pinfunction "L_10") (pintype "output"))
    )
    (net (code "56") (name "unconnected-(AND1-M-Pad11)") (class "Default")
      (node (ref "AND1") (pin "11") (pinfunction "M_11") (pintype "output"))
    )
    (net (code "57") (name "unconnected-(COM1-2IN+-Pad5)") (class "Default")
      (node (ref "COM1") (pin "5") (pinfunction "2IN+_5") (pintype "input"))
    )
    (net (code "58") (name "unconnected-(COM1-2IN--Pad4)") (class "Default")
      (node (ref "COM1") (pin "4") (pinfunction "2IN-_4") (pintype "input"))
    )
    (net (code "59") (name "unconnected-(COM1-2OUT-Pad2)") (class "Default")
      (node (ref "COM1") (pin "2") (pinfunction "2OUT_2") (pintype "output"))
    )
    (net (code "60") (name "unconnected-(COM1-3IN+-Pad9)") (class "Default")
      (node (ref "COM1") (pin "9") (pinfunction "3IN+_9") (pintype "input"))
    )
    (net (code "61") (name "unconnected-(COM1-3IN--Pad8)") (class "Default")
      (node (ref "COM1") (pin "8") (pinfunction "3IN-_8") (pintype "input"))
    )
    (net (code "62") (name "unconnected-(COM1-4IN+-Pad11)") (class "Default")
      (node (ref "COM1") (pin "11") (pinfunction "4IN+_11") (pintype "input"))
    )
    (net (code "63") (name "unconnected-(COM1-4IN--Pad10)") (class "Default")
      (node (ref "COM1") (pin "10") (pinfunction "4IN-_10") (pintype "input"))
    )
    (net (code "64") (name "unconnected-(COM1-OUT3-Pad14)") (class "Default")
      (node (ref "COM1") (pin "14") (pinfunction "OUT3_14") (pintype "output"))
    )
    (net (code "65") (name "unconnected-(COM1-OUT4-Pad13)") (class "Default")
      (node (ref "COM1") (pin "13") (pinfunction "OUT4_13") (pintype "output"))
    )
    (net (code "66") (name "unconnected-(DELAY-B-Pad3)") (class "Default")
      (node (ref "DELAY") (pin "3") (pinfunction "B_3") (pintype "passive"))
    )
    (net (code "67") (name "unconnected-(OR1-E-Pad8)") (class "Default")
      (node (ref "OR1") (pin "8") (pinfunction "E_8") (pintype "input"))
    )
    (net (code "68") (name "unconnected-(OR1-F-Pad9)") (class "Default")
      (node (ref "OR1") (pin "9") (pinfunction "F_9") (pintype "input"))
    )
    (net (code "69") (name "unconnected-(OR1-G-Pad12)") (class "Default")
      (node (ref "OR1") (pin "12") (pinfunction "G_12") (pintype "input"))
    )
    (net (code "70") (name "unconnected-(OR1-H-Pad13)") (class "Default")
      (node (ref "OR1") (pin "13") (pinfunction "H_13") (pintype "input"))
    )
    (net (code "71") (name "unconnected-(OR1-L-Pad10)") (class "Default")
      (node (ref "OR1") (pin "10") (pinfunction "L_10") (pintype "output"))
    )
    (net (code "72") (name "unconnected-(OR1-M-Pad11)") (class "Default")
      (node (ref "OR1") (pin "11") (pinfunction "M_11") (pintype "output"))
    )
    (net (code "73") (name "unconnected-(P1-5A-Pad11)") (class "Default")
      (node (ref "P1") (pin "11") (pinfunction "5A_11") (pintype "input"))
    )
    (net (code "74") (name "unconnected-(P1-5Y-Pad10)") (class "Default")
      (node (ref "P1") (pin "10") (pinfunction "5Y_10") (pintype "output"))
    )
    (net (code "75") (name "unconnected-(Q5-G-Pad2)") (class "Default")
      (node (ref "Q5") (pin "2") (pinfunction "G_2") (pintype "passive"))
    )
    (net (code "76") (name "unconnected-(SR1-NC-Pad2)") (class "Default")
      (node (ref "SR1") (pin "2") (pinfunction "NC_2") (pintype "passive"))
    )
    (net (code "77") (name "unconnected-(SR1-Q4-Pad1)") (class "Default")
      (node (ref "SR1") (pin "1") (pinfunction "Q4_1") (pintype "passive"))
    )
    (net (code "78") (name "unconnected-(SR1-R4-Pad14)") (class "Default")
      (node (ref "SR1") (pin "14") (pinfunction "R4_14") (pintype "passive"))
    )
    (net (code "79") (name "unconnected-(SR1-S4-Pad15)") (class "Default")
      (node (ref "SR1") (pin "15") (pinfunction "S4_15") (pintype "passive"))
    )
  )
)
